# SVR_REVTT_1_0.net
KiCad netlist of a schematic drawn in Altium Designer
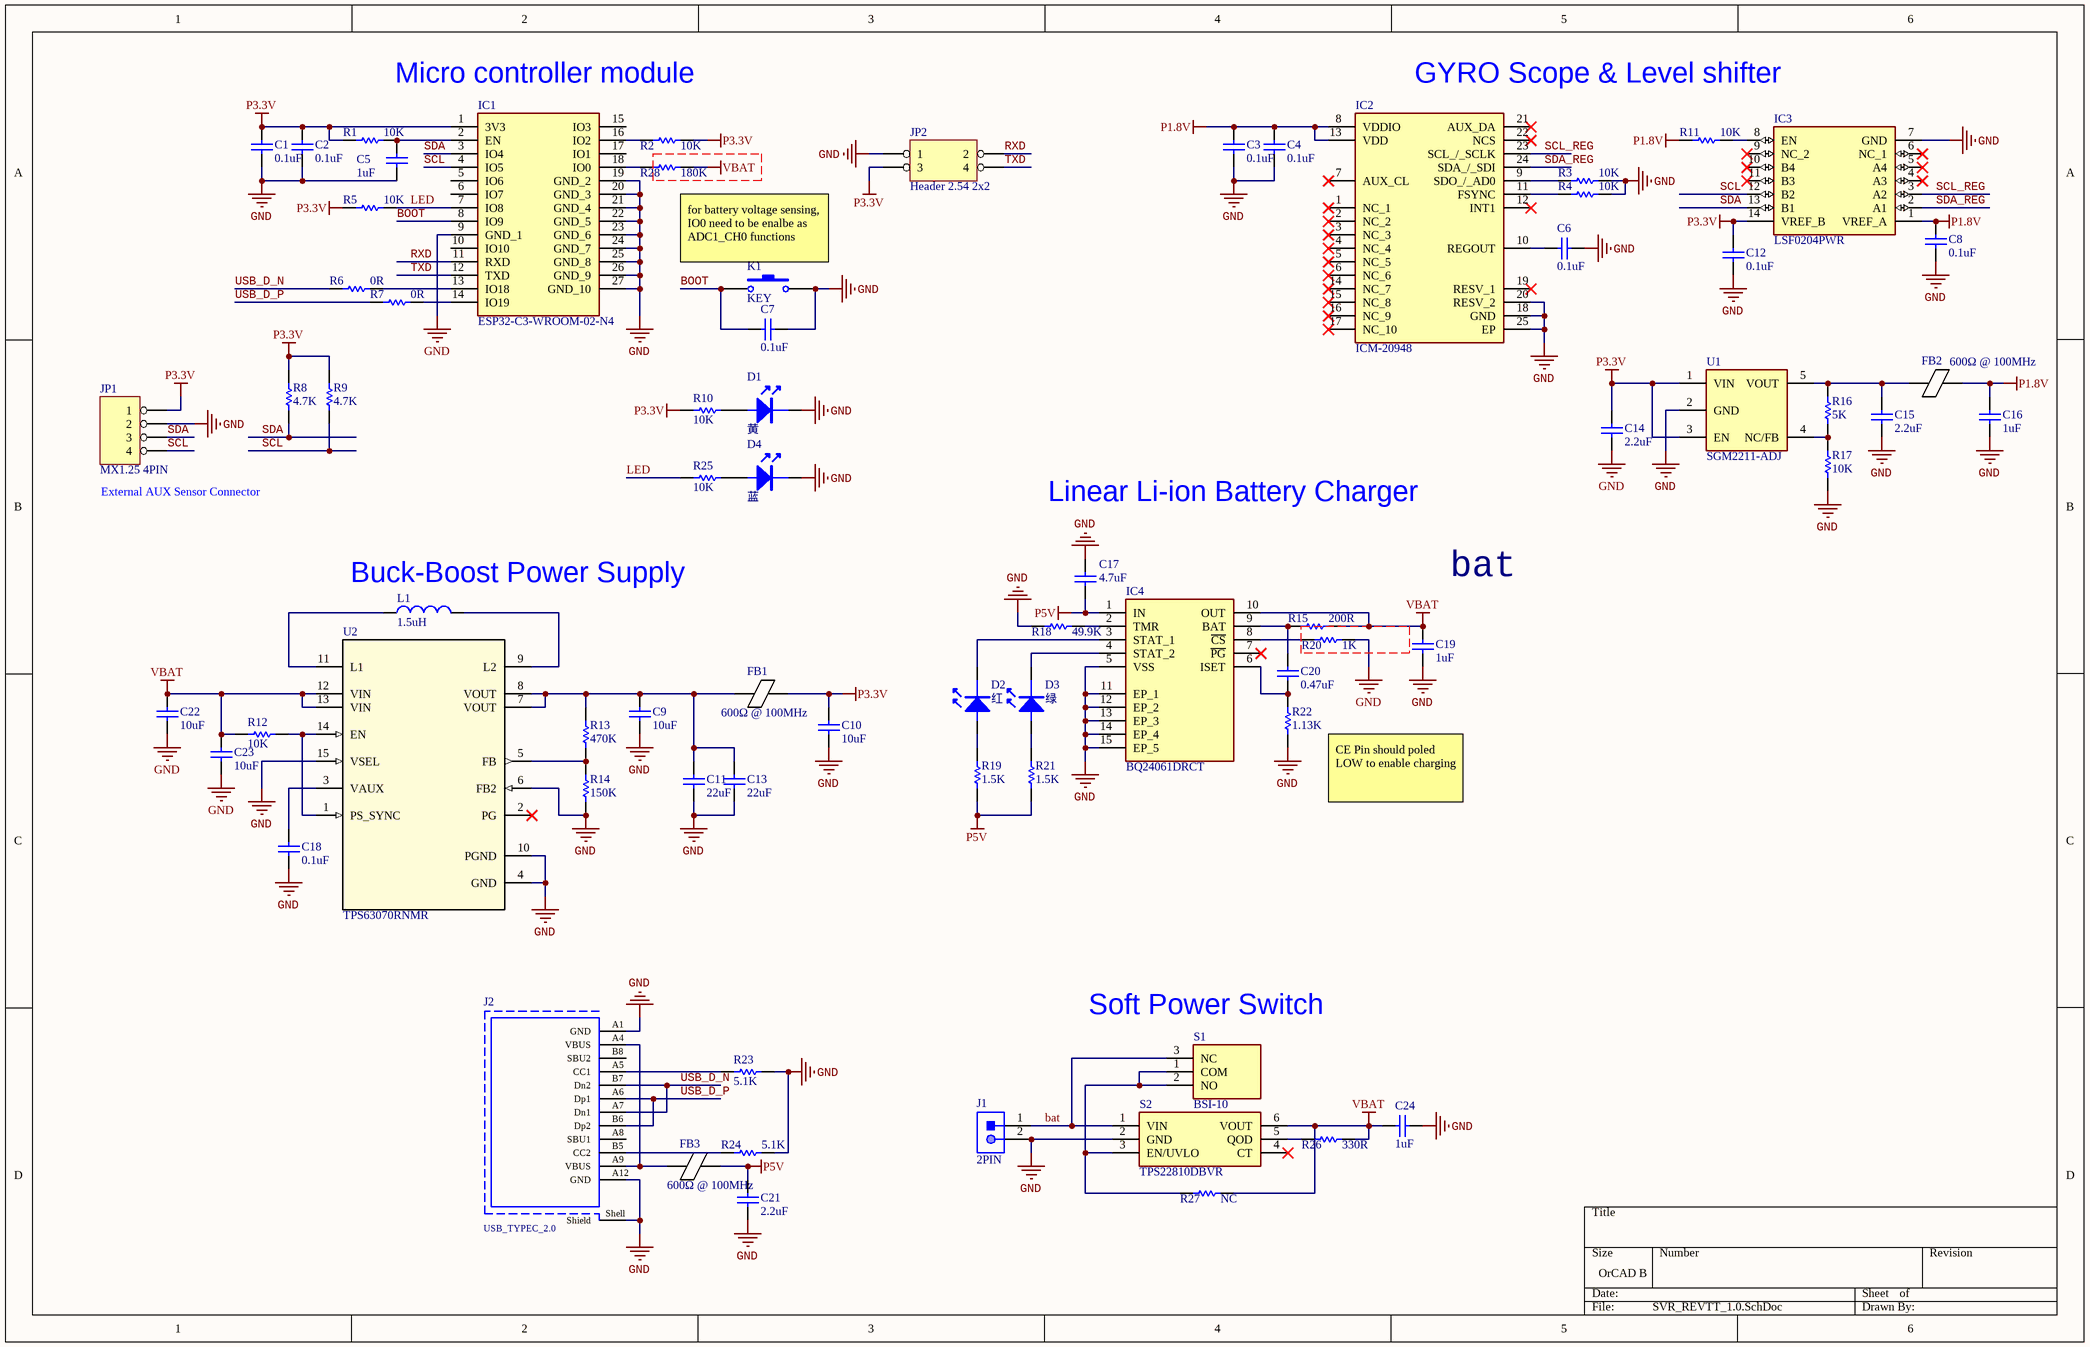
[diagram p0: SVR_REVTT_1.0.SchDoc]

(export (version "E")
  (design (tool "Eeschema 10.0.6"))
  (components
    (comp (ref "C1")
      (value "0.1uF")
      (footprint "0603_C")
      (description "Capacitor")
      (fields (field (name "PUBLISHER") "Altium Limited"))
      (libsource (lib "My Footprint") (part "CAP"))
    )
    (comp (ref "C2")
      (value "0.1uF")
      (footprint "0603_C")
      (description "Capacitor")
      (fields (field (name "PUBLISHER") "Altium Limited"))
      (libsource (lib "My Footprint") (part "CAP"))
    )
    (comp (ref "C3")
      (value "0.1uF")
      (footprint "0603_C")
      (description "Capacitor")
      (fields (field (name "PUBLISHER") "Altium Limited"))
      (libsource (lib "My Footprint") (part "CAP"))
    )
    (comp (ref "C4")
      (value "0.1uF")
      (footprint "0603_C")
      (description "Capacitor")
      (fields (field (name "PUBLISHER") "Altium Limited"))
      (libsource (lib "My Footprint") (part "CAP"))
    )
    (comp (ref "C5")
      (value "1uF")
      (footprint "0603_C")
      (description "Capacitor")
      (fields (field (name "PUBLISHER") "Altium Limited"))
      (libsource (lib "My Footprint") (part "CAP"))
    )
    (comp (ref "C6")
      (value "0.1uF")
      (footprint "0603_C")
      (description "Capacitor")
      (fields (field (name "PUBLISHER") "Altium Limited"))
      (libsource (lib "My Footprint") (part "CAP"))
    )
    (comp (ref "C7")
      (value "0.1uF")
      (footprint "0603_C")
      (description "Capacitor")
      (fields (field (name "PUBLISHER") "Altium Limited"))
      (libsource (lib "My Footprint") (part "CAP"))
    )
    (comp (ref "C8")
      (value "0.1uF")
      (footprint "0603_C")
      (description "Capacitor")
      (fields (field (name "PUBLISHER") "Altium Limited"))
      (libsource (lib "My Footprint") (part "CAP"))
    )
    (comp (ref "C9")
      (value "10uF")
      (footprint "0603_C")
      (description "Capacitor")
      (fields (field (name "PUBLISHER") "Altium Limited"))
      (libsource (lib "My Footprint") (part "CAP"))
    )
    (comp (ref "C10")
      (value "10uF")
      (footprint "0805")
      (description "Capacitor")
      (fields (field (name "PUBLISHER") "Altium Limited"))
      (libsource (lib "My Footprint") (part "CAP"))
    )
    (comp (ref "C11")
      (value "22uF")
      (footprint "0805")
      (description "Capacitor")
      (fields (field (name "PUBLISHER") "Altium Limited"))
      (libsource (lib "My Footprint") (part "CAP"))
    )
    (comp (ref "C12")
      (value "0.1uF")
      (footprint "0603_C")
      (description "Capacitor")
      (fields (field (name "PUBLISHER") "Altium Limited"))
      (libsource (lib "My Footprint") (part "CAP"))
    )
    (comp (ref "C13")
      (value "22uF")
      (footprint "0805")
      (description "Capacitor")
      (fields (field (name "PUBLISHER") "Altium Limited"))
      (libsource (lib "My Footprint") (part "CAP"))
    )
    (comp (ref "C14")
      (value "2.2uF")
      (footprint "0603_C")
      (description "Capacitor")
      (fields (field (name "PUBLISHER") "Altium Limited"))
      (libsource (lib "My Footprint") (part "CAP"))
    )
    (comp (ref "C15")
      (value "2.2uF")
      (footprint "0603_C")
      (description "Capacitor")
      (fields (field (name "PUBLISHER") "Altium Limited"))
      (libsource (lib "My Footprint") (part "CAP"))
    )
    (comp (ref "C16")
      (value "1uF")
      (footprint "0603_C")
      (description "Capacitor")
      (fields (field (name "PUBLISHER") "Altium Limited"))
      (libsource (lib "My Footprint") (part "CAP"))
    )
    (comp (ref "C17")
      (value "4.7uF")
      (footprint "0603_C")
      (description "Capacitor")
      (fields (field (name "PUBLISHER") "Altium Limited"))
      (libsource (lib "My Footprint") (part "CAP"))
    )
    (comp (ref "C18")
      (value "0.1uF")
      (footprint "0603_C")
      (description "Capacitor")
      (fields (field (name "PUBLISHER") "Altium Limited"))
      (libsource (lib "My Footprint") (part "CAP"))
    )
    (comp (ref "C19")
      (value "1uF")
      (footprint "0603_C")
      (description "Capacitor")
      (fields (field (name "PUBLISHER") "Altium Limited"))
      (libsource (lib "My Footprint") (part "CAP"))
    )
    (comp (ref "C20")
      (value "0.47uF")
      (footprint "0603_C")
      (description "Capacitor")
      (fields (field (name "PUBLISHER") "Altium Limited"))
      (libsource (lib "My Footprint") (part "CAP"))
    )
    (comp (ref "C21")
      (value "2.2uF")
      (footprint "0603_C")
      (description "Capacitor")
      (fields (field (name "PUBLISHER") "Altium Limited"))
      (libsource (lib "My Footprint") (part "CAP"))
    )
    (comp (ref "C22")
      (value "10uF")
      (footprint "0805")
      (description "Capacitor")
      (fields (field (name "PUBLISHER") "Altium Limited"))
      (libsource (lib "My Footprint") (part "CAP"))
    )
    (comp (ref "C23")
      (value "10uF")
      (footprint "0805")
      (description "Capacitor")
      (fields (field (name "PUBLISHER") "Altium Limited"))
      (libsource (lib "My Footprint") (part "CAP"))
    )
    (comp (ref "C24")
      (value "1uF")
      (footprint "0603_C")
      (description "Capacitor")
      (fields (field (name "PUBLISHER") "Altium Limited"))
      (libsource (lib "My Footprint") (part "CAP"))
    )
    (comp (ref "D1")
      (value "黄")
      (footprint "0603_LED")
      (description "LED 发光二极管")
      (libsource (lib "My Footprint") (part "LED"))
    )
    (comp (ref "D2")
      (value "红")
      (footprint "0603_LED")
      (description "LED 发光二极管")
      (libsource (lib "My Footprint") (part "LED"))
    )
    (comp (ref "D3")
      (value "绿")
      (footprint "0603_LED")
      (description "LED 发光二极管")
      (libsource (lib "My Footprint") (part "LED"))
    )
    (comp (ref "D4")
      (value "蓝")
      (footprint "0603_LED")
      (description "LED 发光二极管")
      (libsource (lib "My Footprint") (part "LED"))
    )
    (comp (ref "FB1")
      (value "600Ω @ 100MHz")
      (footprint "0805")
      (description "磁珠 600Ω @ 100MHz")
      (libsource (lib "My Footprint") (part "FB"))
    )
    (comp (ref "FB2")
      (value "600Ω @ 100MHz")
      (footprint "0603")
      (description "磁珠 600Ω @ 100MHz")
      (libsource (lib "My Footprint") (part "FB"))
    )
    (comp (ref "FB3")
      (value "600Ω @ 100MHz")
      (footprint "0603")
      (description "磁珠 600Ω @ 100MHz")
      (libsource (lib "My Footprint") (part "FB"))
    )
    (comp (ref "IC1")
      (value "ESP32-C3-WROOM-02-N4")
      (footprint "SamacSys:ESP32C3WROOM02N4")
      (description "Integrated Circuit")
      (fields (field (name "MOUSER PART NUMBER") "356-ESP32C3WROOM02N4"))
      (libsource (lib "SamacSys") (part "ESP32-C3-WROOM-02-N4"))
    )
    (comp (ref "IC2")
      (value "ICM-20948")
      (footprint "SamacSys:QFN40P300X300X105-25N-D")
      (description "Integrated Circuit")
      (fields (field (name "MOUSER PART NUMBER") "410-ICM-20948"))
      (libsource (lib "SamacSys") (part "ICM-20948"))
    )
    (comp (ref "IC3")
      (value "LSF0204PWR")
      (footprint "SamacSys:SOP65P640X120-14N")
      (description "Integrated Circuit")
      (fields (field (name "MOUSER PART NUMBER") "595-LSF0204PWR"))
      (libsource (lib "SamacSys") (part "LSF0204PWR"))
    )
    (comp (ref "IC4")
      (value "BQ24061DRCT")
      (footprint "SamacSys:BQ24060DRCT")
      (description "Integrated Circuit")
      (fields (field (name "MANUFACTURER_PART_NUMBER") "BQ24060DRCT"))
      (libsource (lib "SamacSys") (part "BQ24060DRCT"))
    )
    (comp (ref "J1")
      (value "2PIN")
      (footprint "XH2.54-WI-2P")
      (libsource (lib "My Footprint") (part "HEADER 2PIN"))
    )
    (comp (ref "J2")
      (value "USB_TYPEC_2.0")
      (footprint "USB_TYPEC_2.0_Horizontal_SMT")
      (description "USB 3.1 Type C Receptacle WR-COM, Horizontal, SMT / THT")
      (fields (field (name "PART NUMBER") "632723300011") (field (name "PUBLISHER") "Wurth Elektronik"))
      (libsource (lib "RegenovoPcbLib") (part "USB_TYPEC_2.0"))
    )
    (comp (ref "JP1")
      (value "MX1.25 4PIN")
      (footprint "MX 1.25-WS-4P")
      (libsource (lib "My Footprint") (part "HEADER 4"))
    )
    (comp (ref "JP2")
      (value "Header 2.54 2x2")
      (footprint "header2X2")
      (libsource (lib "My Footprint") (part "HEADER 2X2"))
    )
    (comp (ref "K1")
      (value "KEY")
      (footprint "KEY_2")
      (description "Switch")
      (fields (field (name "PUBLISHER") "Altium Limited"))
      (libsource (lib "My Footprint") (part "KEY_2"))
    )
    (comp (ref "L1")
      (value "1.5uH")
      (footprint "L 1812")
      (description "电感")
      (fields (field (name "Comment") "INDUCTOR") (field (name "PUBLISHER") "Altium Limited"))
      (libsource (lib "RegenovoPcbLib") (part "INDUCTOR"))
    )
    (comp (ref "R1")
      (value "10K")
      (footprint "0603_R")
      (description "Resistor")
      (fields (field (name "PUBLISHER") "Altium Limited"))
      (libsource (lib "My Footprint") (part "RES"))
    )
    (comp (ref "R2")
      (value "10K")
      (footprint "0603_R")
      (description "Resistor")
      (fields (field (name "PUBLISHER") "Altium Limited"))
      (libsource (lib "My Footprint") (part "RES"))
    )
    (comp (ref "R3")
      (value "10K")
      (footprint "0603_R")
      (description "Resistor")
      (fields (field (name "PUBLISHER") "Altium Limited"))
      (libsource (lib "My Footprint") (part "RES"))
    )
    (comp (ref "R4")
      (value "10K")
      (footprint "0603_R")
      (description "Resistor")
      (fields (field (name "PUBLISHER") "Altium Limited"))
      (libsource (lib "My Footprint") (part "RES"))
    )
    (comp (ref "R5")
      (value "10K")
      (footprint "0603_R")
      (description "Resistor")
      (fields (field (name "PUBLISHER") "Altium Limited"))
      (libsource (lib "My Footprint") (part "RES"))
    )
    (comp (ref "R6")
      (value "0R")
      (footprint "0603_R")
      (description "Resistor")
      (fields (field (name "PUBLISHER") "Altium Limited"))
      (libsource (lib "My Footprint") (part "RES"))
    )
    (comp (ref "R7")
      (value "0R")
      (footprint "0603_R")
      (description "Resistor")
      (fields (field (name "PUBLISHER") "Altium Limited"))
      (libsource (lib "My Footprint") (part "RES"))
    )
    (comp (ref "R8")
      (value "4.7K")
      (footprint "0603_R")
      (description "Resistor")
      (fields (field (name "PUBLISHER") "Altium Limited"))
      (libsource (lib "My Footprint") (part "RES"))
    )
    (comp (ref "R9")
      (value "4.7K")
      (footprint "0603_R")
      (description "Resistor")
      (fields (field (name "PUBLISHER") "Altium Limited"))
      (libsource (lib "My Footprint") (part "RES"))
    )
    (comp (ref "R10")
      (value "10K")
      (footprint "0603")
      (description "Resistor")
      (fields (field (name "PUBLISHER") "Altium Limited"))
      (libsource (lib "My Footprint") (part "RES"))
    )
    (comp (ref "R11")
      (value "10K")
      (footprint "0603_R")
      (description "Resistor")
      (fields (field (name "PUBLISHER") "Altium Limited"))
      (libsource (lib "My Footprint") (part "RES"))
    )
    (comp (ref "R12")
      (value "10K")
      (footprint "0603_R")
      (description "Resistor")
      (fields (field (name "PUBLISHER") "Altium Limited"))
      (libsource (lib "My Footprint") (part "RES"))
    )
    (comp (ref "R13")
      (value "470K")
      (footprint "0603_R")
      (description "Resistor")
      (fields (field (name "PUBLISHER") "Altium Limited"))
      (libsource (lib "My Footprint") (part "RES"))
    )
    (comp (ref "R14")
      (value "150K")
      (footprint "0603_R")
      (description "Resistor")
      (fields (field (name "PUBLISHER") "Altium Limited"))
      (libsource (lib "My Footprint") (part "RES"))
    )
    (comp (ref "R15")
      (value "200R")
      (footprint "0603_R")
      (description "Resistor")
      (fields (field (name "PUBLISHER") "Altium Limited"))
      (libsource (lib "My Footprint") (part "RES"))
    )
    (comp (ref "R16")
      (value "5K")
      (footprint "0603")
      (description "Resistor")
      (fields (field (name "PUBLISHER") "Altium Limited"))
      (libsource (lib "My Footprint") (part "RES"))
    )
    (comp (ref "R17")
      (value "10K")
      (footprint "0603")
      (description "Resistor")
      (fields (field (name "PUBLISHER") "Altium Limited"))
      (libsource (lib "My Footprint") (part "RES"))
    )
    (comp (ref "R18")
      (value "49.9K")
      (footprint "0603_R")
      (description "Resistor")
      (fields (field (name "PUBLISHER") "Altium Limited"))
      (libsource (lib "My Footprint") (part "RES"))
    )
    (comp (ref "R19")
      (value "1.5K")
      (footprint "0603_R")
      (description "Resistor")
      (fields (field (name "PUBLISHER") "Altium Limited"))
      (libsource (lib "My Footprint") (part "RES"))
    )
    (comp (ref "R20")
      (value "1K")
      (footprint "0603_R")
      (description "Resistor")
      (fields (field (name "PUBLISHER") "Altium Limited"))
      (libsource (lib "My Footprint") (part "RES"))
    )
    (comp (ref "R21")
      (value "1.5K")
      (footprint "0603_R")
      (description "Resistor")
      (fields (field (name "PUBLISHER") "Altium Limited"))
      (libsource (lib "My Footprint") (part "RES"))
    )
    (comp (ref "R22")
      (value "1.13K")
      (footprint "0603_R")
      (description "Resistor")
      (fields (field (name "PUBLISHER") "Altium Limited"))
      (libsource (lib "My Footprint") (part "RES"))
    )
    (comp (ref "R23")
      (value "5.1K")
      (footprint "0603")
      (description "Resistor")
      (fields (field (name "PUBLISHER") "Altium Limited"))
      (libsource (lib "My Footprint") (part "RES"))
    )
    (comp (ref "R24")
      (value "5.1K")
      (footprint "0603")
      (description "Resistor")
      (fields (field (name "PUBLISHER") "Altium Limited"))
      (libsource (lib "My Footprint") (part "RES"))
    )
    (comp (ref "R25")
      (value "10K")
      (footprint "0603")
      (description "Resistor")
      (fields (field (name "PUBLISHER") "Altium Limited"))
      (libsource (lib "My Footprint") (part "RES"))
    )
    (comp (ref "R26")
      (value "330R")
      (footprint "0603_R")
      (description "Resistor")
      (fields (field (name "PUBLISHER") "Altium Limited"))
      (libsource (lib "My Footprint") (part "RES"))
    )
    (comp (ref "R27")
      (value "NC")
      (footprint "0805")
      (description "Resistor")
      (fields (field (name "PUBLISHER") "Altium Limited"))
      (libsource (lib "My Footprint") (part "RES"))
    )
    (comp (ref "R28")
      (value "180K")
      (footprint "0603_R")
      (description "Resistor")
      (fields (field (name "PUBLISHER") "Altium Limited"))
      (libsource (lib "My Footprint") (part "RES"))
    )
    (comp (ref "S1")
      (value "BSI-10")
      (footprint "BSI10")
      (description "Switch")
      (libsource (lib "SamacSys") (part "BSI-10"))
    )
    (comp (ref "S2")
      (value "TPS22810DBVR")
      (footprint "SamacSys:SOT95P280X145-6N")
      (description "Switch")
      (fields (field (name "MOUSER PART NUMBER") "595-TPS22810DBVR"))
      (libsource (lib "SamacSys") (part "TPS22810DBVR"))
    )
    (comp (ref "U1")
      (value "SGM2211-ADJ")
      (footprint "SOT-23-5")
      (libsource (lib "My Footprint") (part "ADP150"))
    )
    (comp (ref "U2")
      (value "TPS63070RNMR")
      (footprint "RNM0015A")
      (description "Imported")
      (fields (field (name "MANUFACTURER") "Texas Instruments"))
      (libsource (lib "SamacSys") (part "TPS63070RNMR"))
    )
  )
  (nets
    (net (code "1") (name "/BOOT") (class "Default")
      (node (ref "C7") (pin "1") (pinfunction "1_1") (pintype "passive"))
      (node (ref "IC1") (pin "8") (pinfunction "IO9_8") (pintype "passive"))
      (node (ref "K1") (pin "1") (pinfunction "1_1") (pintype "passive"))
    )
    (net (code "2") (name "/LED") (class "Default")
      (node (ref "IC1") (pin "7") (pinfunction "IO8_7") (pintype "passive"))
      (node (ref "R25") (pin "1") (pinfunction "1_1") (pintype "passive"))
      (node (ref "R5") (pin "2") (pinfunction "2_2") (pintype "passive"))
    )
    (net (code "3") (name "/RXD") (class "Default")
      (node (ref "IC1") (pin "11") (pinfunction "RXD_11") (pintype "passive"))
      (node (ref "JP2") (pin "2") (pinfunction "2_2") (pintype "passive"))
    )
    (net (code "4") (name "/SCL") (class "Default")
      (node (ref "IC1") (pin "4") (pinfunction "IO5_4") (pintype "passive"))
      (node (ref "IC3") (pin "12") (pinfunction "B2_12") (pintype "bidirectional"))
      (node (ref "JP1") (pin "4") (pinfunction "4_4") (pintype "passive"))
      (node (ref "R9") (pin "1") (pinfunction "1_1") (pintype "passive"))
    )
    (net (code "5") (name "/SCL_REG") (class "Default")
      (node (ref "IC2") (pin "23") (pinfunction "SCL_/_SCLK_23") (pintype "passive"))
      (node (ref "IC3") (pin "3") (pinfunction "A2_3") (pintype "bidirectional"))
    )
    (net (code "6") (name "/SDA") (class "Default")
      (node (ref "IC1") (pin "3") (pinfunction "IO4_3") (pintype "passive"))
      (node (ref "IC3") (pin "13") (pinfunction "B1_13") (pintype "bidirectional"))
      (node (ref "JP1") (pin "3") (pinfunction "3_3") (pintype "passive"))
      (node (ref "R8") (pin "1") (pinfunction "1_1") (pintype "passive"))
    )
    (net (code "7") (name "/SDA_REG") (class "Default")
      (node (ref "IC2") (pin "24") (pinfunction "SDA_/_SDI_24") (pintype "passive"))
      (node (ref "IC3") (pin "2") (pinfunction "A1_2") (pintype "bidirectional"))
    )
    (net (code "8") (name "/TXD") (class "Default")
      (node (ref "IC1") (pin "12") (pinfunction "TXD_12") (pintype "passive"))
      (node (ref "JP2") (pin "4") (pinfunction "4_4") (pintype "passive"))
    )
    (net (code "9") (name "/USB_D_N") (class "Default")
      (node (ref "J2") (pin "A7") (pinfunction "Dn1_A7") (pintype "passive"))
      (node (ref "J2") (pin "B7") (pinfunction "Dn2_B7") (pintype "passive"))
      (node (ref "R6") (pin "1") (pinfunction "1_1") (pintype "passive"))
    )
    (net (code "10") (name "/USB_D_P") (class "Default")
      (node (ref "J2") (pin "A6") (pinfunction "Dp1_A6") (pintype "passive"))
      (node (ref "J2") (pin "B6") (pinfunction "Dp2_B6") (pintype "passive"))
      (node (ref "R7") (pin "1") (pinfunction "1_1") (pintype "passive"))
    )
    (net (code "11") (name "/bat") (class "Default")
      (node (ref "J1") (pin "1") (pinfunction "1_1") (pintype "passive"))
      (node (ref "S1") (pin "3") (pinfunction "NC_3") (pintype "passive"))
      (node (ref "S2") (pin "1") (pinfunction "VIN_1") (pintype "passive"))
    )
    (net (code "12") (name "GND") (class "Default")
      (node (ref "C1") (pin "1") (pinfunction "1_1") (pintype "passive"))
      (node (ref "C10") (pin "1") (pinfunction "1_1") (pintype "passive"))
      (node (ref "C11") (pin "1") (pinfunction "1_1") (pintype "passive"))
      (node (ref "C12") (pin "2") (pinfunction "2_2") (pintype "passive"))
      (node (ref "C13") (pin "1") (pinfunction "1_1") (pintype "passive"))
      (node (ref "C14") (pin "1") (pinfunction "1_1") (pintype "passive"))
      (node (ref "C15") (pin "1") (pinfunction "1_1") (pintype "passive"))
      (node (ref "C16") (pin "1") (pinfunction "1_1") (pintype "passive"))
      (node (ref "C17") (pin "1") (pinfunction "1_1") (pintype "passive"))
      (node (ref "C18") (pin "2") (pinfunction "2_2") (pintype "passive"))
      (node (ref "C19") (pin "2") (pinfunction "2_2") (pintype "passive"))
      (node (ref "C2") (pin "1") (pinfunction "1_1") (pintype "passive"))
      (node (ref "C21") (pin "1") (pinfunction "1_1") (pintype "passive"))
      (node (ref "C22") (pin "1") (pinfunction "1_1") (pintype "passive"))
      (node (ref "C23") (pin "1") (pinfunction "1_1") (pintype "passive"))
      (node (ref "C24") (pin "2") (pinfunction "2_2") (pintype "passive"))
      (node (ref "C3") (pin "2") (pinfunction "2_2") (pintype "passive"))
      (node (ref "C4") (pin "2") (pinfunction "2_2") (pintype "passive"))
      (node (ref "C5") (pin "1") (pinfunction "1_1") (pintype "passive"))
      (node (ref "C6") (pin "1") (pinfunction "1_1") (pintype "passive"))
      (node (ref "C7") (pin "2") (pinfunction "2_2") (pintype "passive"))
      (node (ref "C8") (pin "2") (pinfunction "2_2") (pintype "passive"))
      (node (ref "C9") (pin "1") (pinfunction "1_1") (pintype "passive"))
      (node (ref "D1") (pin "1") (pinfunction "K_1") (pintype "passive"))
      (node (ref "D4") (pin "1") (pinfunction "K_1") (pintype "passive"))
      (node (ref "IC1") (pin "19") (pinfunction "GND_2_19") (pintype "passive"))
      (node (ref "IC1") (pin "20") (pinfunction "GND_3_20") (pintype "passive"))
      (node (ref "IC1") (pin "21") (pinfunction "GND_4_21") (pintype "passive"))
      (node (ref "IC1") (pin "22") (pinfunction "GND_5_22") (pintype "passive"))
      (node (ref "IC1") (pin "23") (pinfunction "GND_6_23") (pintype "passive"))
      (node (ref "IC1") (pin "24") (pinfunction "GND_7_24") (pintype "passive"))
      (node (ref "IC1") (pin "25") (pinfunction "GND_8_25") (pintype "passive"))
      (node (ref "IC1") (pin "26") (pinfunction "GND_9_26") (pintype "passive"))
      (node (ref "IC1") (pin "27") (pinfunction "GND_10_27") (pintype "passive"))
      (node (ref "IC1") (pin "9") (pinfunction "GND_1_9") (pintype "passive"))
      (node (ref "IC2") (pin "18") (pinfunction "GND_18") (pintype "passive"))
      (node (ref "IC2") (pin "20") (pinfunction "RESV_2_20") (pintype "passive"))
      (node (ref "IC2") (pin "25") (pinfunction "EP_25") (pintype "passive"))
      (node (ref "IC3") (pin "7") (pinfunction "GND_7") (pintype "power_in"))
      (node (ref "IC4") (pin "11") (pinfunction "EP_1_11") (pintype "passive"))
      (node (ref "IC4") (pin "12") (pinfunction "EP_2_12") (pintype "passive"))
      (node (ref "IC4") (pin "13") (pinfunction "EP_3_13") (pintype "passive"))
      (node (ref "IC4") (pin "14") (pinfunction "EP_4_14") (pintype "passive"))
      (node (ref "IC4") (pin "15") (pinfunction "EP_5_15") (pintype "passive"))
      (node (ref "IC4") (pin "5") (pinfunction "VSS_5") (pintype "passive"))
      (node (ref "J1") (pin "2") (pinfunction "2_2") (pintype "passive"))
      (node (ref "J2") (pin "A1") (pinfunction "GND_A1") (pintype "passive"))
      (node (ref "J2") (pin "A12") (pinfunction "GND_A12") (pintype "passive"))
      (node (ref "J2") (pin "Shell") (pinfunction "Shield_Shell") (pintype "passive"))
      (node (ref "JP1") (pin "2") (pinfunction "2_2") (pintype "passive"))
      (node (ref "JP2") (pin "1") (pinfunction "1_1") (pintype "passive"))
      (node (ref "K1") (pin "2") (pinfunction "2_2") (pintype "passive"))
      (node (ref "R14") (pin "2") (pinfunction "2_2") (pintype "passive"))
      (node (ref "R17") (pin "1") (pinfunction "1_1") (pintype "passive"))
      (node (ref "R18") (pin "2") (pinfunction "2_2") (pintype "passive"))
      (node (ref "R20") (pin "1") (pinfunction "1_1") (pintype "passive"))
      (node (ref "R22") (pin "1") (pinfunction "1_1") (pintype "passive"))
      (node (ref "R23") (pin "2") (pinfunction "2_2") (pintype "passive"))
      (node (ref "R24") (pin "2") (pinfunction "2_2") (pintype "passive"))
      (node (ref "R3") (pin "2") (pinfunction "2_2") (pintype "passive"))
      (node (ref "R4") (pin "2") (pinfunction "2_2") (pintype "passive"))
      (node (ref "S2") (pin "2") (pinfunction "GND_2") (pintype "passive"))
      (node (ref "U1") (pin "2") (pinfunction "GND_2") (pintype "passive"))
      (node (ref "U2") (pin "10") (pinfunction "PGND_10") (pintype "power_in"))
      (node (ref "U2") (pin "15") (pinfunction "VSEL_15") (pintype "input"))
      (node (ref "U2") (pin "4") (pinfunction "GND_4") (pintype "power_in"))
      (node (ref "U2") (pin "6") (pinfunction "FB2_6") (pintype "input"))
    )
    (net (code "13") (name "Net-(C11-Pad2)") (class "Default")
      (node (ref "C11") (pin "2") (pinfunction "2_2") (pintype "passive"))
      (node (ref "C13") (pin "2") (pinfunction "2_2") (pintype "passive"))
      (node (ref "C9") (pin "2") (pinfunction "2_2") (pintype "passive"))
      (node (ref "FB1") (pin "1") (pinfunction "1_1") (pintype "passive"))
      (node (ref "R13") (pin "1") (pinfunction "1_1") (pintype "passive"))
      (node (ref "U2") (pin "7") (pinfunction "VOUT_7") (pintype "power_in"))
      (node (ref "U2") (pin "8") (pinfunction "VOUT_8") (pintype "power_in"))
    )
    (net (code "14") (name "Net-(D1-A)") (class "Default")
      (node (ref "D1") (pin "2") (pinfunction "A_2") (pintype "passive"))
      (node (ref "R10") (pin "2") (pinfunction "2_2") (pintype "passive"))
    )
    (net (code "15") (name "Net-(D2-A)") (class "Default")
      (node (ref "D2") (pin "2") (pinfunction "A_2") (pintype "passive"))
      (node (ref "R19") (pin "1") (pinfunction "1_1") (pintype "passive"))
    )
    (net (code "16") (name "Net-(D2-K)") (class "Default")
      (node (ref "D2") (pin "1") (pinfunction "K_1") (pintype "passive"))
      (node (ref "IC4") (pin "3") (pinfunction "STAT_1_3") (pintype "passive"))
    )
    (net (code "17") (name "Net-(D3-A)") (class "Default")
      (node (ref "D3") (pin "2") (pinfunction "A_2") (pintype "passive"))
      (node (ref "R21") (pin "1") (pinfunction "1_1") (pintype "passive"))
    )
    (net (code "18") (name "Net-(D3-K)") (class "Default")
      (node (ref "D3") (pin "1") (pinfunction "K_1") (pintype "passive"))
      (node (ref "IC4") (pin "4") (pinfunction "STAT_2_4") (pintype "passive"))
    )
    (net (code "19") (name "Net-(D4-A)") (class "Default")
      (node (ref "D4") (pin "2") (pinfunction "A_2") (pintype "passive"))
      (node (ref "R25") (pin "2") (pinfunction "2_2") (pintype "passive"))
    )
    (net (code "20") (name "Net-(FB3-Pad1)") (class "Default")
      (node (ref "FB3") (pin "1") (pinfunction "1_1") (pintype "passive"))
      (node (ref "J2") (pin "A4") (pinfunction "VBUS_A4") (pintype "passive"))
      (node (ref "J2") (pin "A9") (pinfunction "VBUS_A9") (pintype "passive"))
    )
    (net (code "21") (name "Net-(IC1-EN)") (class "Default")
      (node (ref "C5") (pin "2") (pinfunction "2_2") (pintype "passive"))
      (node (ref "IC1") (pin "2") (pinfunction "EN_2") (pintype "passive"))
      (node (ref "R1") (pin "2") (pinfunction "2_2") (pintype "passive"))
    )
    (net (code "22") (name "Net-(IC1-IO0)") (class "Default")
      (node (ref "IC1") (pin "18") (pinfunction "IO0_18") (pintype "passive"))
      (node (ref "R28") (pin "1") (pinfunction "1_1") (pintype "passive"))
    )
    (net (code "23") (name "Net-(IC1-IO2)") (class "Default")
      (node (ref "IC1") (pin "16") (pinfunction "IO2_16") (pintype "passive"))
      (node (ref "R2") (pin "1") (pinfunction "1_1") (pintype "passive"))
    )
    (net (code "24") (name "Net-(IC1-IO18)") (class "Default")
      (node (ref "IC1") (pin "13") (pinfunction "IO18_13") (pintype "passive"))
      (node (ref "R6") (pin "2") (pinfunction "2_2") (pintype "passive"))
    )
    (net (code "25") (name "Net-(IC1-IO19)") (class "Default")
      (node (ref "IC1") (pin "14") (pinfunction "IO19_14") (pintype "passive"))
      (node (ref "R7") (pin "2") (pinfunction "2_2") (pintype "passive"))
    )
    (net (code "26") (name "Net-(IC2-FSYNC)") (class "Default")
      (node (ref "IC2") (pin "11") (pinfunction "FSYNC_11") (pintype "passive"))
      (node (ref "R4") (pin "1") (pinfunction "1_1") (pintype "passive"))
    )
    (net (code "27") (name "Net-(IC2-REGOUT)") (class "Default")
      (node (ref "C6") (pin "2") (pinfunction "2_2") (pintype "passive"))
      (node (ref "IC2") (pin "10") (pinfunction "REGOUT_10") (pintype "passive"))
    )
    (net (code "28") (name "Net-(IC2-SDO_{slash}_AD0)") (class "Default")
      (node (ref "IC2") (pin "9") (pinfunction "SDO_/_AD0_9") (pintype "passive"))
      (node (ref "R3") (pin "1") (pinfunction "1_1") (pintype "passive"))
    )
    (net (code "29") (name "Net-(IC3-EN)") (class "Default")
      (node (ref "IC3") (pin "8") (pinfunction "EN_8") (pintype "bidirectional"))
      (node (ref "R11") (pin "2") (pinfunction "2_2") (pintype "passive"))
    )
    (net (code "30") (name "Net-(IC4-BAT)") (class "Default")
      (node (ref "C20") (pin "2") (pinfunction "2_2") (pintype "passive"))
      (node (ref "IC4") (pin "9") (pinfunction "BAT_9") (pintype "passive"))
      (node (ref "R15") (pin "2") (pinfunction "2_2") (pintype "passive"))
    )
    (net (code "31") (name "Net-(IC4-ISET)") (class "Default")
      (node (ref "C20") (pin "1") (pinfunction "1_1") (pintype "passive"))
      (node (ref "IC4") (pin "6") (pinfunction "ISET_6") (pintype "passive"))
      (node (ref "R22") (pin "2") (pinfunction "2_2") (pintype "passive"))
    )
    (net (code "32") (name "Net-(IC4-TMR)") (class "Default")
      (node (ref "IC4") (pin "2") (pinfunction "TMR_2") (pintype "passive"))
      (node (ref "R18") (pin "1") (pinfunction "1_1") (pintype "passive"))
    )
    (net (code "33") (name "Net-(IC4-~{CS})") (class "Default")
      (node (ref "IC4") (pin "8") (pinfunction "~{CS}_8") (pintype "passive"))
      (node (ref "R20") (pin "2") (pinfunction "2_2") (pintype "passive"))
    )
    (net (code "34") (name "Net-(J2-CC1)") (class "Default")
      (node (ref "J2") (pin "A5") (pinfunction "CC1_A5") (pintype "passive"))
      (node (ref "R23") (pin "1") (pinfunction "1_1") (pintype "passive"))
    )
    (net (code "35") (name "Net-(J2-CC2)") (class "Default")
      (node (ref "J2") (pin "B5") (pinfunction "CC2_B5") (pintype "passive"))
      (node (ref "R24") (pin "1") (pinfunction "1_1") (pintype "passive"))
    )
    (net (code "36") (name "Net-(S1-COM)") (class "Default")
      (node (ref "R27") (pin "1") (pinfunction "1_1") (pintype "passive"))
      (node (ref "S1") (pin "1") (pinfunction "COM_1") (pintype "passive"))
      (node (ref "S1") (pin "2") (pinfunction "NO_2") (pintype "passive"))
      (node (ref "S2") (pin "3") (pinfunction "EN/UVLO_3") (pintype "passive"))
    )
    (net (code "37") (name "Net-(S2-QOD)") (class "Default")
      (node (ref "R26") (pin "1") (pinfunction "1_1") (pintype "passive"))
      (node (ref "S2") (pin "5") (pinfunction "QOD_5") (pintype "passive"))
    )
    (net (code "38") (name "Net-(U1-NC{slash}FB)") (class "Default")
      (node (ref "R16") (pin "1") (pinfunction "1_1") (pintype "passive"))
      (node (ref "R17") (pin "2") (pinfunction "2_2") (pintype "passive"))
      (node (ref "U1") (pin "4") (pinfunction "NC/FB_4") (pintype "passive"))
    )
    (net (code "39") (name "Net-(U1-VOUT)") (class "Default")
      (node (ref "C15") (pin "2") (pinfunction "2_2") (pintype "passive"))
      (node (ref "FB2") (pin "1") (pinfunction "1_1") (pintype "passive"))
      (node (ref "R16") (pin "2") (pinfunction "2_2") (pintype "passive"))
      (node (ref "U1") (pin "5") (pinfunction "VOUT_5") (pintype "passive"))
    )
    (net (code "40") (name "Net-(U2-EN)") (class "Default")
      (node (ref "R12") (pin "1") (pinfunction "1_1") (pintype "passive"))
      (node (ref "U2") (pin "1") (pinfunction "PS_SYNC_1") (pintype "input"))
      (node (ref "U2") (pin "14") (pinfunction "EN_14") (pintype "input"))
    )
    (net (code "41") (name "Net-(U2-FB)") (class "Default")
      (node (ref "R13") (pin "2") (pinfunction "2_2") (pintype "passive"))
      (node (ref "R14") (pin "1") (pinfunction "1_1") (pintype "passive"))
      (node (ref "U2") (pin "5") (pinfunction "FB_5") (pintype "output"))
    )
    (net (code "42") (name "Net-(U2-L1)") (class "Default")
      (node (ref "L1") (pin "1") (pinfunction "1_1") (pintype "passive"))
      (node (ref "U2") (pin "11") (pinfunction "L1_11") (pintype "passive"))
    )
    (net (code "43") (name "Net-(U2-L2)") (class "Default")
      (node (ref "L1") (pin "2") (pinfunction "2_2") (pintype "passive"))
      (node (ref "U2") (pin "9") (pinfunction "L2_9") (pintype "passive"))
    )
    (net (code "44") (name "Net-(U2-VAUX)") (class "Default")
      (node (ref "C18") (pin "1") (pinfunction "1_1") (pintype "passive"))
      (node (ref "U2") (pin "3") (pinfunction "VAUX_3") (pintype "passive"))
    )
    (net (code "45") (name "P1.8V") (class "Default")
      (node (ref "C16") (pin "2") (pinfunction "2_2") (pintype "passive"))
      (node (ref "C3") (pin "1") (pinfunction "1_1") (pintype "passive"))
      (node (ref "C4") (pin "1") (pinfunction "1_1") (pintype "passive"))
      (node (ref "C8") (pin "1") (pinfunction "1_1") (pintype "passive"))
      (node (ref "FB2") (pin "2") (pinfunction "2_2") (pintype "passive"))
      (node (ref "IC2") (pin "13") (pinfunction "VDD_13") (pintype "passive"))
      (node (ref "IC2") (pin "8") (pinfunction "VDDIO_8") (pintype "passive"))
      (node (ref "IC3") (pin "1") (pinfunction "VREF_A_1") (pintype "power_in"))
      (node (ref "R11") (pin "1") (pinfunction "1_1") (pintype "passive"))
    )
    (net (code "46") (name "P3.3V") (class "Default")
      (node (ref "C1") (pin "2") (pinfunction "2_2") (pintype "passive"))
      (node (ref "C10") (pin "2") (pinfunction "2_2") (pintype "passive"))
      (node (ref "C12") (pin "1") (pinfunction "1_1") (pintype "passive"))
      (node (ref "C14") (pin "2") (pinfunction "2_2") (pintype "passive"))
      (node (ref "C2") (pin "2") (pinfunction "2_2") (pintype "passive"))
      (node (ref "FB1") (pin "2") (pinfunction "2_2") (pintype "passive"))
      (node (ref "IC1") (pin "1") (pinfunction "3V3_1") (pintype "passive"))
      (node (ref "IC3") (pin "14") (pinfunction "VREF_B_14") (pintype "power_in"))
      (node (ref "JP1") (pin "1") (pinfunction "1_1") (pintype "passive"))
      (node (ref "JP2") (pin "3") (pinfunction "3_3") (pintype "passive"))
      (node (ref "R1") (pin "1") (pinfunction "1_1") (pintype "passive"))
      (node (ref "R10") (pin "1") (pinfunction "1_1") (pintype "passive"))
      (node (ref "R2") (pin "2") (pinfunction "2_2") (pintype "passive"))
      (node (ref "R5") (pin "1") (pinfunction "1_1") (pintype "passive"))
      (node (ref "R8") (pin "2") (pinfunction "2_2") (pintype "passive"))
      (node (ref "R9") (pin "2") (pinfunction "2_2") (pintype "passive"))
      (node (ref "U1") (pin "1") (pinfunction "VIN_1") (pintype "passive"))
      (node (ref "U1") (pin "3") (pinfunction "EN_3") (pintype "passive"))
    )
    (net (code "47") (name "P5V") (class "Default")
      (node (ref "C17") (pin "2") (pinfunction "2_2") (pintype "passive"))
      (node (ref "C21") (pin "2") (pinfunction "2_2") (pintype "passive"))
      (node (ref "FB3") (pin "2") (pinfunction "2_2") (pintype "passive"))
      (node (ref "IC4") (pin "1") (pinfunction "IN_1") (pintype "passive"))
      (node (ref "R19") (pin "2") (pinfunction "2_2") (pintype "passive"))
      (node (ref "R21") (pin "2") (pinfunction "2_2") (pintype "passive"))
    )
    (net (code "48") (name "VBAT") (class "Default")
      (node (ref "C19") (pin "1") (pinfunction "1_1") (pintype "passive"))
      (node (ref "C22") (pin "2") (pinfunction "2_2") (pintype "passive"))
      (node (ref "C23") (pin "2") (pinfunction "2_2") (pintype "passive"))
      (node (ref "C24") (pin "1") (pinfunction "1_1") (pintype "passive"))
      (node (ref "IC4") (pin "10") (pinfunction "OUT_10") (pintype "passive"))
      (node (ref "R12") (pin "2") (pinfunction "2_2") (pintype "passive"))
      (node (ref "R15") (pin "1") (pinfunction "1_1") (pintype "passive"))
      (node (ref "R26") (pin "2") (pinfunction "2_2") (pintype "passive"))
      (node (ref "R27") (pin "2") (pinfunction "2_2") (pintype "passive"))
      (node (ref "R28") (pin "2") (pinfunction "2_2") (pintype "passive"))
      (node (ref "S2") (pin "6") (pinfunction "VOUT_6") (pintype "passive"))
      (node (ref "U2") (pin "12") (pinfunction "VIN_12") (pintype "power_in"))
      (node (ref "U2") (pin "13") (pinfunction "VIN_13") (pintype "power_in"))
    )
    (net (code "49") (name "unconnected-(IC1-IO1-Pad17)") (class "Default")
      (node (ref "IC1") (pin "17") (pinfunction "IO1_17") (pintype "passive"))
    )
    (net (code "50") (name "unconnected-(IC1-IO3-Pad15)") (class "Default")
      (node (ref "IC1") (pin "15") (pinfunction "IO3_15") (pintype "passive"))
    )
    (net (code "51") (name "unconnected-(IC1-IO6-Pad5)") (class "Default")
      (node (ref "IC1") (pin "5") (pinfunction "IO6_5") (pintype "passive"))
    )
    (net (code "52") (name "unconnected-(IC1-IO7-Pad6)") (class "Default")
      (node (ref "IC1") (pin "6") (pinfunction "IO7_6") (pintype "passive"))
    )
    (net (code "53") (name "unconnected-(IC1-IO10-Pad10)") (class "Default")
      (node (ref "IC1") (pin "10") (pinfunction "IO10_10") (pintype "passive"))
    )
    (net (code "54") (name "unconnected-(IC2-AUX_CL-Pad7)") (class "Default")
      (node (ref "IC2") (pin "7") (pinfunction "AUX_CL_7") (pintype "passive+no_connect"))
    )
    (net (code "55") (name "unconnected-(IC2-AUX_DA-Pad21)") (class "Default")
      (node (ref "IC2") (pin "21") (pinfunction "AUX_DA_21") (pintype "passive+no_connect"))
    )
    (net (code "56") (name "unconnected-(IC2-INT1-Pad12)") (class "Default")
      (node (ref "IC2") (pin "12") (pinfunction "INT1_12") (pintype "passive+no_connect"))
    )
    (net (code "57") (name "unconnected-(IC2-NCS-Pad22)") (class "Default")
      (node (ref "IC2") (pin "22") (pinfunction "NCS_22") (pintype "passive+no_connect"))
    )
    (net (code "58") (name "unconnected-(IC2-NC_1-Pad1)") (class "Default")
      (node (ref "IC2") (pin "1") (pinfunction "NC_1_1") (pintype "passive+no_connect"))
    )
    (net (code "59") (name "unconnected-(IC2-NC_2-Pad2)") (class "Default")
      (node (ref "IC2") (pin "2") (pinfunction "NC_2_2") (pintype "passive+no_connect"))
    )
    (net (code "60") (name "unconnected-(IC2-NC_3-Pad3)") (class "Default")
      (node (ref "IC2") (pin "3") (pinfunction "NC_3_3") (pintype "passive+no_connect"))
    )
    (net (code "61") (name "unconnected-(IC2-NC_4-Pad4)") (class "Default")
      (node (ref "IC2") (pin "4") (pinfunction "NC_4_4") (pintype "passive+no_connect"))
    )
    (net (code "62") (name "unconnected-(IC2-NC_5-Pad5)") (class "Default")
      (node (ref "IC2") (pin "5") (pinfunction "NC_5_5") (pintype "passive+no_connect"))
    )
    (net (code "63") (name "unconnected-(IC2-NC_6-Pad6)") (class "Default")
      (node (ref "IC2") (pin "6") (pinfunction "NC_6_6") (pintype "passive+no_connect"))
    )
    (net (code "64") (name "unconnected-(IC2-NC_7-Pad14)") (class "Default")
      (node (ref "IC2") (pin "14") (pinfunction "NC_7_14") (pintype "passive+no_connect"))
    )
    (net (code "65") (name "unconnected-(IC2-NC_8-Pad15)") (class "Default")
      (node (ref "IC2") (pin "15") (pinfunction "NC_8_15") (pintype "passive+no_connect"))
    )
    (net (code "66") (name "unconnected-(IC2-NC_9-Pad16)") (class "Default")
      (node (ref "IC2") (pin "16") (pinfunction "NC_9_16") (pintype "passive+no_connect"))
    )
    (net (code "67") (name "unconnected-(IC2-NC_10-Pad17)") (class "Default")
      (node (ref "IC2") (pin "17") (pinfunction "NC_10_17") (pintype "passive+no_connect"))
    )
    (net (code "68") (name "unconnected-(IC2-RESV_1-Pad19)") (class "Default")
      (node (ref "IC2") (pin "19") (pinfunction "RESV_1_19") (pintype "passive+no_connect"))
    )
    (net (code "69") (name "unconnected-(IC3-A3-Pad4)") (class "Default")
      (node (ref "IC3") (pin "4") (pinfunction "A3_4") (pintype "bidirectional+no_connect"))
    )
    (net (code "70") (name "unconnected-(IC3-A4-Pad5)") (class "Default")
      (node (ref "IC3") (pin "5") (pinfunction "A4_5") (pintype "bidirectional+no_connect"))
    )
    (net (code "71") (name "unconnected-(IC3-B3-Pad11)") (class "Default")
      (node (ref "IC3") (pin "11") (pinfunction "B3_11") (pintype "bidirectional+no_connect"))
    )
    (net (code "72") (name "unconnected-(IC3-B4-Pad10)") (class "Default")
      (node (ref "IC3") (pin "10") (pinfunction "B4_10") (pintype "bidirectional+no_connect"))
    )
    (net (code "73") (name "unconnected-(IC3-NC_1-Pad6)") (class "Default")
      (node (ref "IC3") (pin "6") (pinfunction "NC_1_6") (pintype "bidirectional+no_connect"))
    )
    (net (code "74") (name "unconnected-(IC3-NC_2-Pad9)") (class "Default")
      (node (ref "IC3") (pin "9") (pinfunction "NC_2_9") (pintype "bidirectional+no_connect"))
    )
    (net (code "75") (name "unconnected-(IC4-~{PG}-Pad7)") (class "Default")
      (node (ref "IC4") (pin "7") (pinfunction "~{PG}_7") (pintype "passive+no_connect"))
    )
    (net (code "76") (name "unconnected-(J2-SBU1-PadA8)") (class "Default")
      (node (ref "J2") (pin "A8") (pinfunction "SBU1_A8") (pintype "passive"))
    )
    (net (code "77") (name "unconnected-(J2-SBU2-PadB8)") (class "Default")
      (node (ref "J2") (pin "B8") (pinfunction "SBU2_B8") (pintype "passive"))
    )
    (net (code "78") (name "unconnected-(S2-CT-Pad4)") (class "Default")
      (node (ref "S2") (pin "4") (pinfunction "CT_4") (pintype "passive+no_connect"))
    )
    (net (code "79") (name "unconnected-(U2-PG-Pad2)") (class "Default")
      (node (ref "U2") (pin "2") (pinfunction "PG_2") (pintype "open_collector+no_connect"))
    )
  )
)
